# FT2232Circuit.net
KiCad netlist of a schematic drawn in Altium Designer
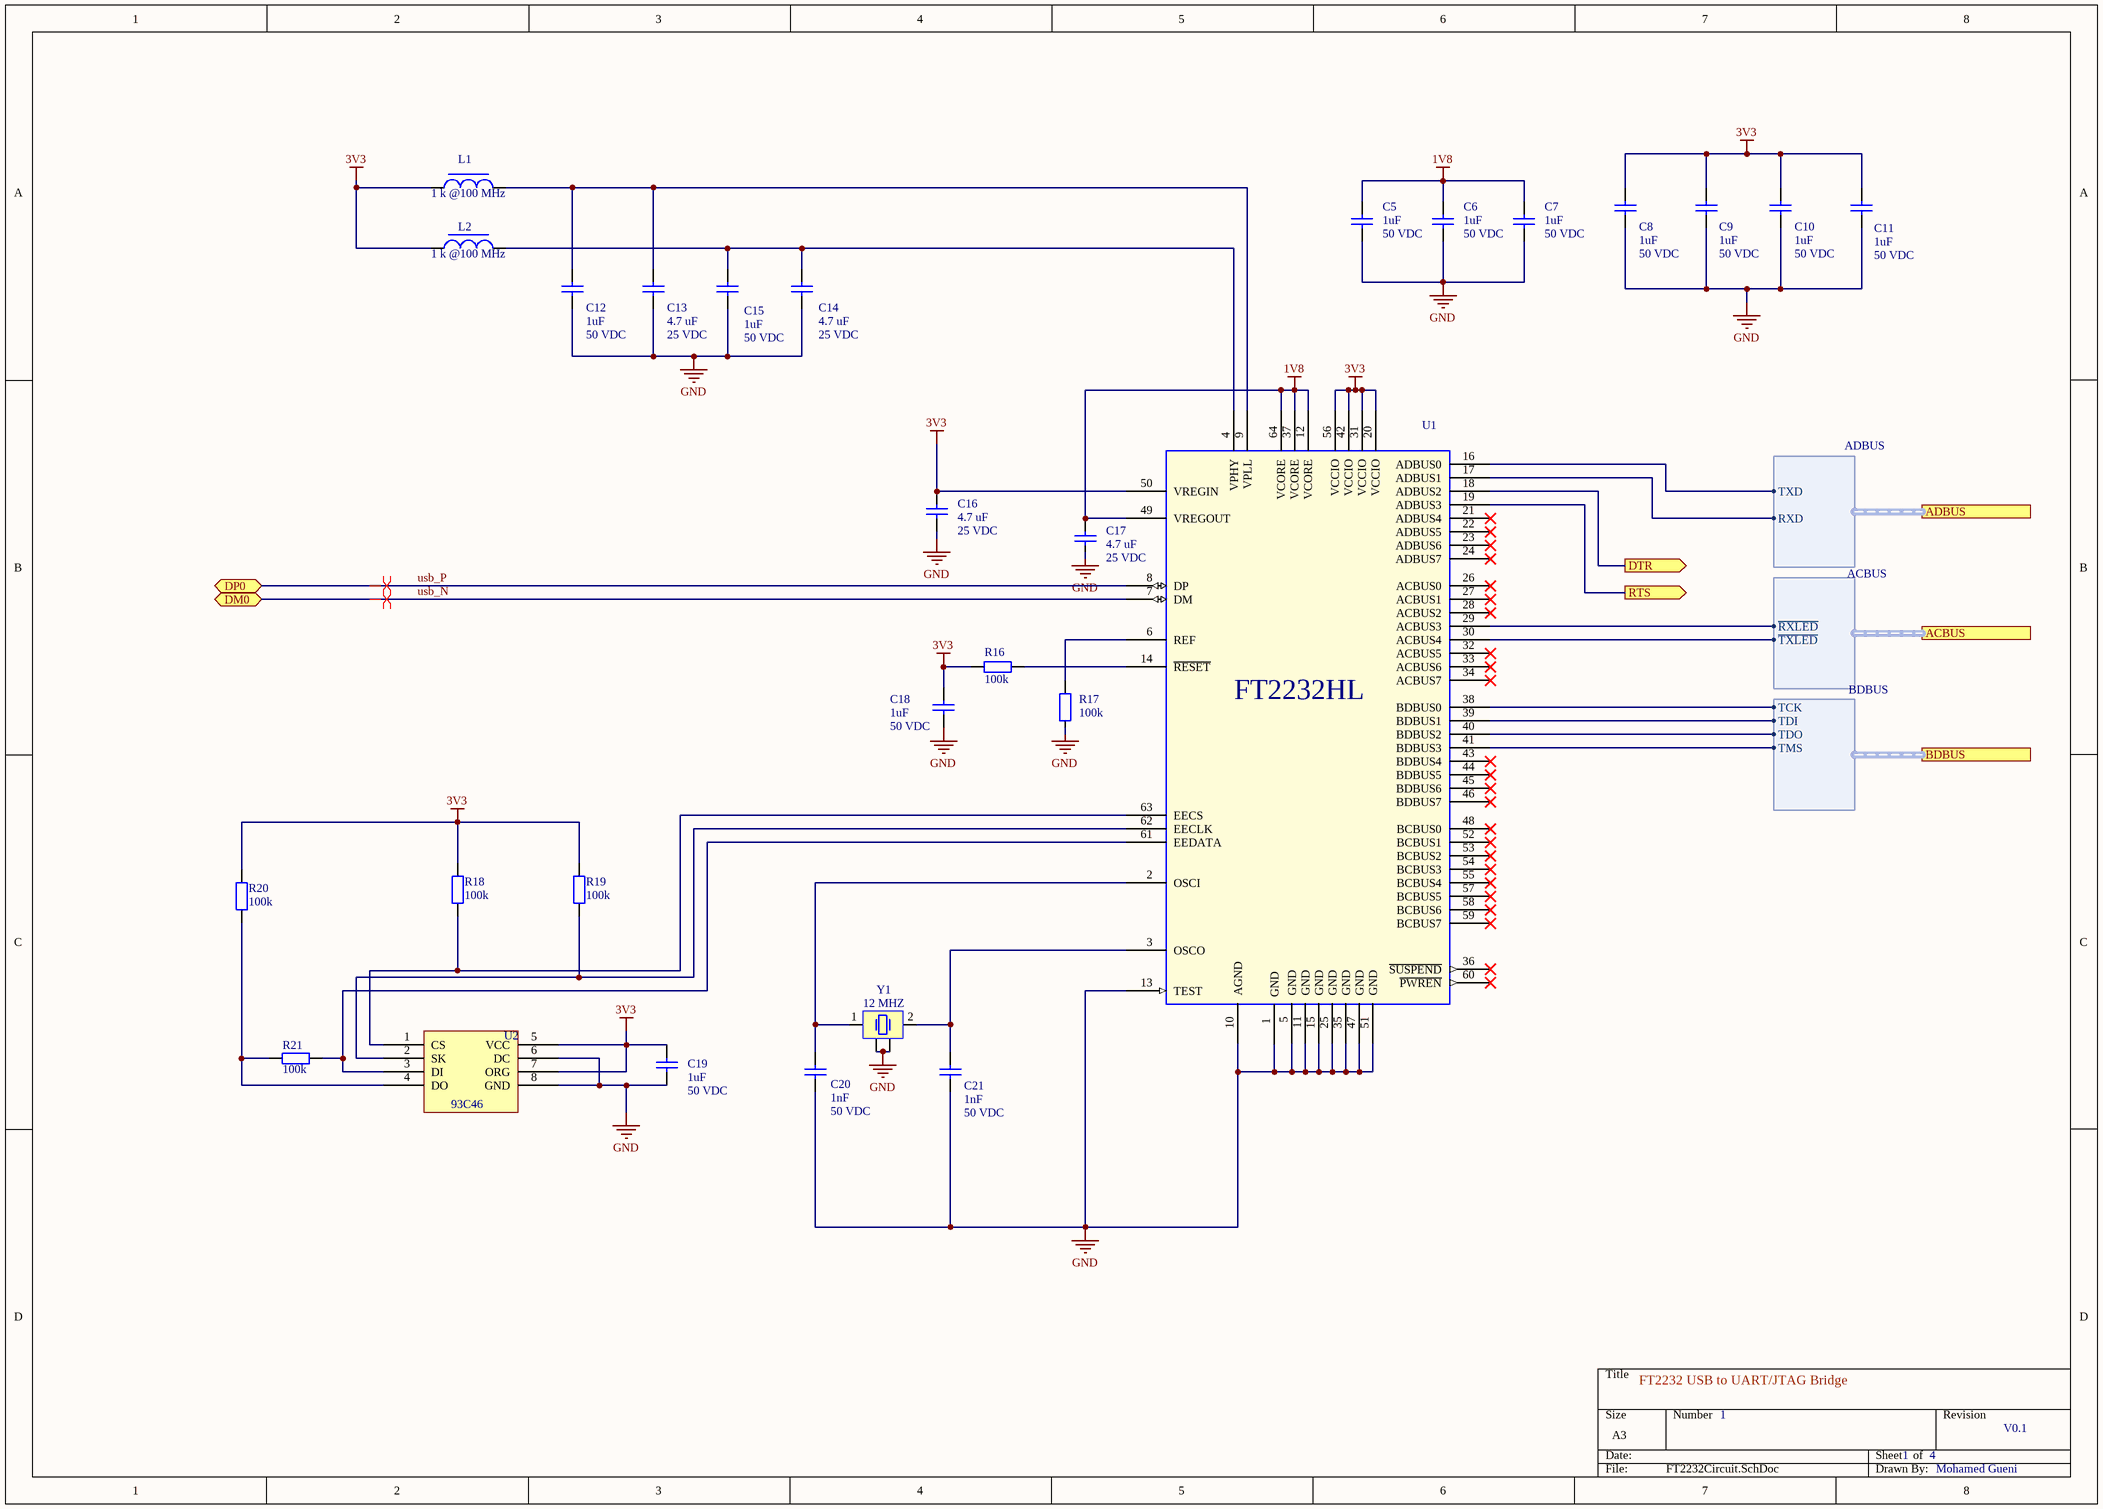
[diagram p0: FT2232Circuit.SchDoc]

(export (version "E")
  (design (tool "Eeschema 10.0.6"))
  (components
    (comp (ref "C5")
      (value "Capacitor")
      (footprint "CAP-0603")
      (fields
        (field (name "VALUE 1") "1uF")
        (field (name "VALUE 2") "50 VDC")
        (field (name "PART NUMBER") "C-000000011")
      )
      (libsource (lib "DATABASE") (part "Capacitor"))
    )
    (comp (ref "C6")
      (value "Capacitor")
      (footprint "CAP-0603")
      (fields
        (field (name "VALUE 1") "1uF")
        (field (name "VALUE 2") "50 VDC")
        (field (name "PART NUMBER") "C-000000011")
      )
      (libsource (lib "DATABASE") (part "Capacitor"))
    )
    (comp (ref "C7")
      (value "Capacitor")
      (footprint "CAP-0603")
      (fields
        (field (name "VALUE 1") "1uF")
        (field (name "VALUE 2") "50 VDC")
        (field (name "PART NUMBER") "C-000000011")
      )
      (libsource (lib "DATABASE") (part "Capacitor"))
    )
    (comp (ref "C8")
      (value "Capacitor")
      (footprint "CAP-0603")
      (fields
        (field (name "VALUE 1") "1uF")
        (field (name "VALUE 2") "50 VDC")
        (field (name "PART NUMBER") "C-000000011")
      )
      (libsource (lib "DATABASE") (part "Capacitor"))
    )
    (comp (ref "C9")
      (value "Capacitor")
      (footprint "CAP-0603")
      (fields
        (field (name "VALUE 1") "1uF")
        (field (name "VALUE 2") "50 VDC")
        (field (name "PART NUMBER") "C-000000011")
      )
      (libsource (lib "DATABASE") (part "Capacitor"))
    )
    (comp (ref "C10")
      (value "Capacitor")
      (footprint "CAP-0603")
      (fields
        (field (name "VALUE 1") "1uF")
        (field (name "VALUE 2") "50 VDC")
        (field (name "PART NUMBER") "C-000000011")
      )
      (libsource (lib "DATABASE") (part "Capacitor"))
    )
    (comp (ref "C11")
      (value "Capacitor")
      (footprint "CAP-0603")
      (fields
        (field (name "VALUE 1") "1uF")
        (field (name "VALUE 2") "50 VDC")
        (field (name "PART NUMBER") "C-000000011")
      )
      (libsource (lib "DATABASE") (part "Capacitor"))
    )
    (comp (ref "C12")
      (value "Capacitor")
      (footprint "CAP-0603")
      (fields
        (field (name "VALUE 1") "1uF")
        (field (name "VALUE 2") "50 VDC")
        (field (name "PART NUMBER") "C-000000011")
      )
      (libsource (lib "DATABASE") (part "Capacitor"))
    )
    (comp (ref "C13")
      (value "Capacitor")
      (footprint "CAP-0603")
      (fields
        (field (name "PART NUMBER") "C-000000007")
        (field (name "VALUE 1") "4.7 uF")
        (field (name "VALUE 2") "25 VDC")
      )
      (libsource (lib "DATABASE") (part "Capacitor"))
    )
    (comp (ref "C14")
      (value "Capacitor")
      (footprint "CAP-0603")
      (fields
        (field (name "PART NUMBER") "C-000000007")
        (field (name "VALUE 1") "4.7 uF")
        (field (name "VALUE 2") "25 VDC")
      )
      (libsource (lib "DATABASE") (part "Capacitor"))
    )
    (comp (ref "C15")
      (value "Capacitor")
      (footprint "CAP-0603")
      (fields
        (field (name "VALUE 1") "1uF")
        (field (name "VALUE 2") "50 VDC")
        (field (name "PART NUMBER") "C-000000011")
      )
      (libsource (lib "DATABASE") (part "Capacitor"))
    )
    (comp (ref "C16")
      (value "Capacitor")
      (footprint "CAP-0603")
      (fields
        (field (name "VALUE 1") "4.7 uF")
        (field (name "VALUE 2") "25 VDC")
        (field (name "PART NUMBER") "C-000000007")
      )
      (libsource (lib "DATABASE") (part "Capacitor"))
    )
    (comp (ref "C17")
      (value "Capacitor")
      (footprint "CAP-0603")
      (fields
        (field (name "VALUE 1") "4.7 uF")
        (field (name "VALUE 2") "25 VDC")
        (field (name "PART NUMBER") "C-000000007")
      )
      (libsource (lib "DATABASE") (part "Capacitor"))
    )
    (comp (ref "C18")
      (value "Capacitor")
      (footprint "CAP-0603")
      (fields
        (field (name "VALUE 1") "1uF")
        (field (name "VALUE 2") "50 VDC")
        (field (name "PART NUMBER") "C-000000011")
      )
      (libsource (lib "DATABASE") (part "Capacitor"))
    )
    (comp (ref "C19")
      (value "Capacitor")
      (footprint "CAP-0603")
      (fields
        (field (name "VALUE 1") "1uF")
        (field (name "VALUE 2") "50 VDC")
        (field (name "PART NUMBER") "C-000000011")
      )
      (libsource (lib "DATABASE") (part "Capacitor"))
    )
    (comp (ref "C20")
      (value "Capacitor")
      (footprint "CAP-0603")
      (fields
        (field (name "VALUE 1") "1nF")
        (field (name "VALUE 2") "50 VDC")
        (field (name "PART NUMBER") "C-000000010")
      )
      (libsource (lib "DATABASE") (part "Capacitor"))
    )
    (comp (ref "C21")
      (value "Capacitor")
      (footprint "CAP-0603")
      (fields
        (field (name "VALUE 1") "1nF")
        (field (name "VALUE 2") "50 VDC")
        (field (name "PART NUMBER") "C-000000010")
      )
      (libsource (lib "DATABASE") (part "Capacitor"))
    )
    (comp (ref "L1")
      (value "MPZ1608S102A")
      (footprint "RESC3216X18N")
      (fields (field (name "VALUE 1") "1 k @100 MHz"))
      (libsource (lib "DATABASE") (part "Ferrit"))
    )
    (comp (ref "L2")
      (value "MPZ1608S102A")
      (footprint "RESC3216X18N")
      (fields (field (name "VALUE 1") "1 k @100 MHz"))
      (libsource (lib "DATABASE") (part "Ferrit"))
    )
    (comp (ref "R16")
      (value "Resistor")
      (footprint "R0603")
      (fields (field (name "VALUE 1") "100k") (field (name "PART NUMBER") "R-000000002"))
      (libsource (lib "") (part "Resistor_2"))
    )
    (comp (ref "R17")
      (value "Resistor")
      (footprint "R0603")
      (fields (field (name "VALUE 1") "100k") (field (name "PART NUMBER") "R-000000002"))
      (libsource (lib "DATABASE") (part "Resistor"))
    )
    (comp (ref "R18")
      (value "Resistor")
      (footprint "R0603")
      (fields (field (name "VALUE 1") "100k") (field (name "PART NUMBER") "R-000000002"))
      (libsource (lib "DATABASE") (part "Resistor"))
    )
    (comp (ref "R19")
      (value "Resistor")
      (footprint "R0603")
      (fields (field (name "VALUE 1") "100k") (field (name "PART NUMBER") "R-000000002"))
      (libsource (lib "DATABASE") (part "Resistor"))
    )
    (comp (ref "R20")
      (value "Resistor")
      (footprint "R0603")
      (fields (field (name "VALUE 1") "100k") (field (name "PART NUMBER") "R-000000002"))
      (libsource (lib "DATABASE") (part "Resistor"))
    )
    (comp (ref "R21")
      (value "Resistor")
      (footprint "R0603")
      (fields (field (name "VALUE 1") "100k") (field (name "PART NUMBER") "R-000000002"))
      (libsource (lib "") (part "Resistor_1"))
    )
    (comp (ref "U1")
      (value "FT2232HL-REEL")
      (footprint "TSQFP50P1200X1200X160-64N")
      (fields (field (name "PART NUMBER") "U-000000002"))
      (libsource (lib "DATABASE") (part "FT2232HL-REEL"))
    )
    (comp (ref "U2")
      (value "93C46")
      (footprint "SOIC127P600X175-8N")
      (fields (field (name "PART NUMBER") "U-000000003"))
      (libsource (lib "DATABASE") (part "93C46"))
    )
    (comp (ref "Y1")
      (value "XTAL4")
      (footprint "WE-4XTAL3.2x2.5mm")
      (fields (field (name "VALUE 1") "12 MHZ"))
      (libsource (lib "DATABASE") (part "XTAL4"))
    )
  )
  (nets
    (net (code "4") (name "/DTR") (class "Default")
      (node (ref "U1") (pin "18") (pinfunction "ADBUS2_18") (pintype "passive"))
    )
    (net (code "5") (name "/RTS") (class "Default")
      (node (ref "U1") (pin "19") (pinfunction "ADBUS3_19") (pintype "passive"))
    )
    (net (code "6") (name "/RXD") (class "Default")
      (node (ref "U1") (pin "17") (pinfunction "ADBUS1_17") (pintype "passive"))
    )
    (net (code "7") (name "/TCK") (class "Default")
      (node (ref "U1") (pin "38") (pinfunction "BDBUS0_38") (pintype "passive"))
    )
    (net (code "8") (name "/TDI") (class "Default")
      (node (ref "U1") (pin "39") (pinfunction "BDBUS1_39") (pintype "passive"))
    )
    (net (code "9") (name "/TDO") (class "Default")
      (node (ref "U1") (pin "40") (pinfunction "BDBUS2_40") (pintype "passive"))
    )
    (net (code "10") (name "/TMS") (class "Default")
      (node (ref "U1") (pin "41") (pinfunction "BDBUS3_41") (pintype "passive"))
    )
    (net (code "11") (name "/TXD") (class "Default")
      (node (ref "U1") (pin "16") (pinfunction "ADBUS0_16") (pintype "passive"))
    )
    (net (code "12") (name "/usb_N") (class "Default")
      (node (ref "U1") (pin "7") (pinfunction "DM_7") (pintype "bidirectional"))
    )
    (net (code "13") (name "/usb_P") (class "Default")
      (node (ref "U1") (pin "8") (pinfunction "DP_8") (pintype "bidirectional"))
    )
    (net (code "17") (name "/~{RXLED}") (class "Default")
      (node (ref "U1") (pin "29") (pinfunction "ACBUS3_29") (pintype "passive"))
    )
    (net (code "18") (name "/~{TXLED}") (class "Default")
      (node (ref "U1") (pin "30") (pinfunction "ACBUS4_30") (pintype "passive"))
    )
    (net (code "19") (name "1V8") (class "Default")
      (node (ref "C17") (pin "2") (pinfunction "2_2") (pintype "passive"))
      (node (ref "C5") (pin "2") (pinfunction "2_2") (pintype "passive"))
      (node (ref "C6") (pin "2") (pinfunction "2_2") (pintype "passive"))
      (node (ref "C7") (pin "2") (pinfunction "2_2") (pintype "passive"))
      (node (ref "U1") (pin "12") (pinfunction "VCORE_12") (pintype "power_in"))
      (node (ref "U1") (pin "37") (pinfunction "VCORE_37") (pintype "power_in"))
      (node (ref "U1") (pin "49") (pinfunction "VREGOUT_49") (pintype "power_in"))
      (node (ref "U1") (pin "64") (pinfunction "VCORE_64") (pintype "power_in"))
    )
    (net (code "20") (name "3V3") (class "Default")
      (node (ref "C10") (pin "2") (pinfunction "2_2") (pintype "passive"))
      (node (ref "C11") (pin "2") (pinfunction "2_2") (pintype "passive"))
      (node (ref "C16") (pin "2") (pinfunction "2_2") (pintype "passive"))
      (node (ref "C18") (pin "2") (pinfunction "2_2") (pintype "passive"))
      (node (ref "C19") (pin "2") (pinfunction "2_2") (pintype "passive"))
      (node (ref "C8") (pin "2") (pinfunction "2_2") (pintype "passive"))
      (node (ref "C9") (pin "2") (pinfunction "2_2") (pintype "passive"))
      (node (ref "L1") (pin "2") (pinfunction "2_2") (pintype "passive"))
      (node (ref "L2") (pin "2") (pinfunction "2_2") (pintype "passive"))
      (node (ref "R16") (pin "1") (pinfunction "1_1") (pintype "passive"))
      (node (ref "R18") (pin "2") (pinfunction "2_2") (pintype "passive"))
      (node (ref "R19") (pin "2") (pinfunction "2_2") (pintype "passive"))
      (node (ref "R20") (pin "2") (pinfunction "2_2") (pintype "passive"))
      (node (ref "U1") (pin "20") (pinfunction "VCCIO_20") (pintype "power_in"))
      (node (ref "U1") (pin "31") (pinfunction "VCCIO_31") (pintype "power_in"))
      (node (ref "U1") (pin "42") (pinfunction "VCCIO_42") (pintype "power_in"))
      (node (ref "U1") (pin "50") (pinfunction "VREGIN_50") (pintype "power_in"))
      (node (ref "U1") (pin "56") (pinfunction "VCCIO_56") (pintype "power_in"))
      (node (ref "U2") (pin "5") (pinfunction "VCC_5") (pintype "power_in"))
      (node (ref "U2") (pin "7") (pinfunction "ORG_7") (pintype "passive"))
    )
    (net (code "21") (name "GND") (class "Default")
      (node (ref "C10") (pin "1") (pinfunction "1_1") (pintype "passive"))
      (node (ref "C11") (pin "1") (pinfunction "1_1") (pintype "passive"))
      (node (ref "C12") (pin "1") (pinfunction "1_1") (pintype "passive"))
      (node (ref "C13") (pin "1") (pinfunction "1_1") (pintype "passive"))
      (node (ref "C14") (pin "1") (pinfunction "1_1") (pintype "passive"))
      (node (ref "C15") (pin "1") (pinfunction "1_1") (pintype "passive"))
      (node (ref "C16") (pin "1") (pinfunction "1_1") (pintype "passive"))
      (node (ref "C17") (pin "1") (pinfunction "1_1") (pintype "passive"))
      (node (ref "C18") (pin "1") (pinfunction "1_1") (pintype "passive"))
      (node (ref "C19") (pin "1") (pinfunction "1_1") (pintype "passive"))
      (node (ref "C20") (pin "1") (pinfunction "1_1") (pintype "passive"))
      (node (ref "C21") (pin "1") (pinfunction "1_1") (pintype "passive"))
      (node (ref "C5") (pin "1") (pinfunction "1_1") (pintype "passive"))
      (node (ref "C6") (pin "1") (pinfunction "1_1") (pintype "passive"))
      (node (ref "C7") (pin "1") (pinfunction "1_1") (pintype "passive"))
      (node (ref "C8") (pin "1") (pinfunction "1_1") (pintype "passive"))
      (node (ref "C9") (pin "1") (pinfunction "1_1") (pintype "passive"))
      (node (ref "R17") (pin "1") (pinfunction "1_1") (pintype "passive"))
      (node (ref "U1") (pin "1") (pinfunction "GND_1") (pintype "power_in"))
      (node (ref "U1") (pin "10") (pinfunction "AGND_10") (pintype "power_in"))
      (node (ref "U1") (pin "11") (pinfunction "GND_11") (pintype "power_in"))
      (node (ref "U1") (pin "13") (pinfunction "TEST_13") (pintype "input"))
      (node (ref "U1") (pin "15") (pinfunction "GND_15") (pintype "power_in"))
      (node (ref "U1") (pin "25") (pinfunction "GND_25") (pintype "power_in"))
      (node (ref "U1") (pin "35") (pinfunction "GND_35") (pintype "power_in"))
      (node (ref "U1") (pin "47") (pinfunction "GND_47") (pintype "power_in"))
      (node (ref "U1") (pin "5") (pinfunction "GND_5") (pintype "power_in"))
      (node (ref "U1") (pin "51") (pinfunction "GND_51") (pintype "power_in"))
      (node (ref "U2") (pin "6") (pinfunction "DC_6") (pintype "passive"))
      (node (ref "U2") (pin "8") (pinfunction "GND_8") (pintype "power_in"))
      (node (ref "Y1") (pin "GND1") (pinfunction "GND1_GND1") (pintype "passive"))
      (node (ref "Y1") (pin "GND2") (pinfunction "GND2_GND2") (pintype "passive"))
    )
    (net (code "22") (name "Net-(U1-EECLK)") (class "Default")
      (node (ref "R19") (pin "1") (pinfunction "1_1") (pintype "passive"))
      (node (ref "U1") (pin "62") (pinfunction "EECLK_62") (pintype "passive"))
      (node (ref "U2") (pin "2") (pinfunction "SK_2") (pintype "passive"))
    )
    (net (code "23") (name "Net-(U1-EECS)") (class "Default")
      (node (ref "R18") (pin "1") (pinfunction "1_1") (pintype "passive"))
      (node (ref "U1") (pin "63") (pinfunction "EECS_63") (pintype "passive"))
      (node (ref "U2") (pin "1") (pinfunction "CS_1") (pintype "passive"))
    )
    (net (code "24") (name "Net-(U1-EEDATA)") (class "Default")
      (node (ref "R21") (pin "1") (pinfunction "1_1") (pintype "passive"))
      (node (ref "U1") (pin "61") (pinfunction "EEDATA_61") (pintype "passive"))
      (node (ref "U2") (pin "3") (pinfunction "DI_3") (pintype "passive"))
    )
    (net (code "25") (name "Net-(U1-OSCI)") (class "Default")
      (node (ref "C20") (pin "2") (pinfunction "2_2") (pintype "passive"))
      (node (ref "U1") (pin "2") (pinfunction "OSCI_2") (pintype "passive"))
      (node (ref "Y1") (pin "1") (pinfunction "OSC1_1") (pintype "passive"))
    )
    (net (code "26") (name "Net-(U1-OSCO)") (class "Default")
      (node (ref "C21") (pin "2") (pinfunction "2_2") (pintype "passive"))
      (node (ref "U1") (pin "3") (pinfunction "OSCO_3") (pintype "passive"))
      (node (ref "Y1") (pin "2") (pinfunction "OSC2_2") (pintype "passive"))
    )
    (net (code "27") (name "Net-(U1-REF)") (class "Default")
      (node (ref "R17") (pin "2") (pinfunction "2_2") (pintype "passive"))
      (node (ref "U1") (pin "6") (pinfunction "REF_6") (pintype "passive"))
    )
    (net (code "28") (name "Net-(U1-VPHY)") (class "Default")
      (node (ref "C14") (pin "2") (pinfunction "2_2") (pintype "passive"))
      (node (ref "C15") (pin "2") (pinfunction "2_2") (pintype "passive"))
      (node (ref "L2") (pin "1") (pinfunction "1_1") (pintype "passive"))
      (node (ref "U1") (pin "4") (pinfunction "VPHY_4") (pintype "power_in"))
    )
    (net (code "29") (name "Net-(U1-VPLL)") (class "Default")
      (node (ref "C12") (pin "2") (pinfunction "2_2") (pintype "passive"))
      (node (ref "C13") (pin "2") (pinfunction "2_2") (pintype "passive"))
      (node (ref "L1") (pin "1") (pinfunction "1_1") (pintype "passive"))
      (node (ref "U1") (pin "9") (pinfunction "VPLL_9") (pintype "power_in"))
    )
    (net (code "30") (name "Net-(U1-~{RESET})") (class "Default")
      (node (ref "R16") (pin "2") (pinfunction "2_2") (pintype "passive"))
      (node (ref "U1") (pin "14") (pinfunction "~{RESET}_14") (pintype "passive"))
    )
    (net (code "31") (name "Net-(U2-DO)") (class "Default")
      (node (ref "R20") (pin "1") (pinfunction "1_1") (pintype "passive"))
      (node (ref "R21") (pin "2") (pinfunction "2_2") (pintype "passive"))
      (node (ref "U2") (pin "4") (pinfunction "DO_4") (pintype "passive"))
    )
    (net (code "32") (name "unconnected-(U1-ACBUS0-Pad26)") (class "Default")
      (node (ref "U1") (pin "26") (pinfunction "ACBUS0_26") (pintype "passive+no_connect"))
    )
    (net (code "33") (name "unconnected-(U1-ACBUS1-Pad27)") (class "Default")
      (node (ref "U1") (pin "27") (pinfunction "ACBUS1_27") (pintype "passive+no_connect"))
    )
    (net (code "34") (name "unconnected-(U1-ACBUS2-Pad28)") (class "Default")
      (node (ref "U1") (pin "28") (pinfunction "ACBUS2_28") (pintype "passive+no_connect"))
    )
    (net (code "35") (name "unconnected-(U1-ACBUS5-Pad32)") (class "Default")
      (node (ref "U1") (pin "32") (pinfunction "ACBUS5_32") (pintype "passive+no_connect"))
    )
    (net (code "36") (name "unconnected-(U1-ACBUS6-Pad33)") (class "Default")
      (node (ref "U1") (pin "33") (pinfunction "ACBUS6_33") (pintype "passive+no_connect"))
    )
    (net (code "37") (name "unconnected-(U1-ACBUS7-Pad34)") (class "Default")
      (node (ref "U1") (pin "34") (pinfunction "ACBUS7_34") (pintype "passive+no_connect"))
    )
    (net (code "38") (name "unconnected-(U1-ADBUS4-Pad21)") (class "Default")
      (node (ref "U1") (pin "21") (pinfunction "ADBUS4_21") (pintype "passive+no_connect"))
    )
    (net (code "39") (name "unconnected-(U1-ADBUS5-Pad22)") (class "Default")
      (node (ref "U1") (pin "22") (pinfunction "ADBUS5_22") (pintype "passive+no_connect"))
    )
    (net (code "40") (name "unconnected-(U1-ADBUS6-Pad23)") (class "Default")
      (node (ref "U1") (pin "23") (pinfunction "ADBUS6_23") (pintype "passive+no_connect"))
    )
    (net (code "41") (name "unconnected-(U1-ADBUS7-Pad24)") (class "Default")
      (node (ref "U1") (pin "24") (pinfunction "ADBUS7_24") (pintype "passive+no_connect"))
    )
    (net (code "42") (name "unconnected-(U1-BCBUS0-Pad48)") (class "Default")
      (node (ref "U1") (pin "48") (pinfunction "BCBUS0_48") (pintype "passive+no_connect"))
    )
    (net (code "43") (name "unconnected-(U1-BCBUS1-Pad52)") (class "Default")
      (node (ref "U1") (pin "52") (pinfunction "BCBUS1_52") (pintype "passive+no_connect"))
    )
    (net (code "44") (name "unconnected-(U1-BCBUS2-Pad53)") (class "Default")
      (node (ref "U1") (pin "53") (pinfunction "BCBUS2_53") (pintype "passive+no_connect"))
    )
    (net (code "45") (name "unconnected-(U1-BCBUS3-Pad54)") (class "Default")
      (node (ref "U1") (pin "54") (pinfunction "BCBUS3_54") (pintype "passive+no_connect"))
    )
    (net (code "46") (name "unconnected-(U1-BCBUS4-Pad55)") (class "Default")
      (node (ref "U1") (pin "55") (pinfunction "BCBUS4_55") (pintype "passive+no_connect"))
    )
    (net (code "47") (name "unconnected-(U1-BCBUS5-Pad57)") (class "Default")
      (node (ref "U1") (pin "57") (pinfunction "BCBUS5_57") (pintype "passive+no_connect"))
    )
    (net (code "48") (name "unconnected-(U1-BCBUS6-Pad58)") (class "Default")
      (node (ref "U1") (pin "58") (pinfunction "BCBUS6_58") (pintype "passive+no_connect"))
    )
    (net (code "49") (name "unconnected-(U1-BCBUS7-Pad59)") (class "Default")
      (node (ref "U1") (pin "59") (pinfunction "BCBUS7_59") (pintype "passive+no_connect"))
    )
    (net (code "50") (name "unconnected-(U1-BDBUS4-Pad43)") (class "Default")
      (node (ref "U1") (pin "43") (pinfunction "BDBUS4_43") (pintype "passive+no_connect"))
    )
    (net (code "51") (name "unconnected-(U1-BDBUS5-Pad44)") (class "Default")
      (node (ref "U1") (pin "44") (pinfunction "BDBUS5_44") (pintype "passive+no_connect"))
    )
    (net (code "52") (name "unconnected-(U1-BDBUS6-Pad45)") (class "Default")
      (node (ref "U1") (pin "45") (pinfunction "BDBUS6_45") (pintype "passive+no_connect"))
    )
    (net (code "53") (name "unconnected-(U1-BDBUS7-Pad46)") (class "Default")
      (node (ref "U1") (pin "46") (pinfunction "BDBUS7_46") (pintype "passive+no_connect"))
    )
    (net (code "54") (name "unconnected-(U1-~{PWREN}-Pad60)") (class "Default")
      (node (ref "U1") (pin "60") (pinfunction "~{PWREN}_60") (pintype "output+no_connect"))
    )
    (net (code "55") (name "unconnected-(U1-~{SUSPEND}-Pad36)") (class "Default")
      (node (ref "U1") (pin "36") (pinfunction "~{SUSPEND}_36") (pintype "output+no_connect"))
    )
  )
)
